# ZHSD-DDR3L.net
KiCad netlist of a schematic drawn in Altium Designer
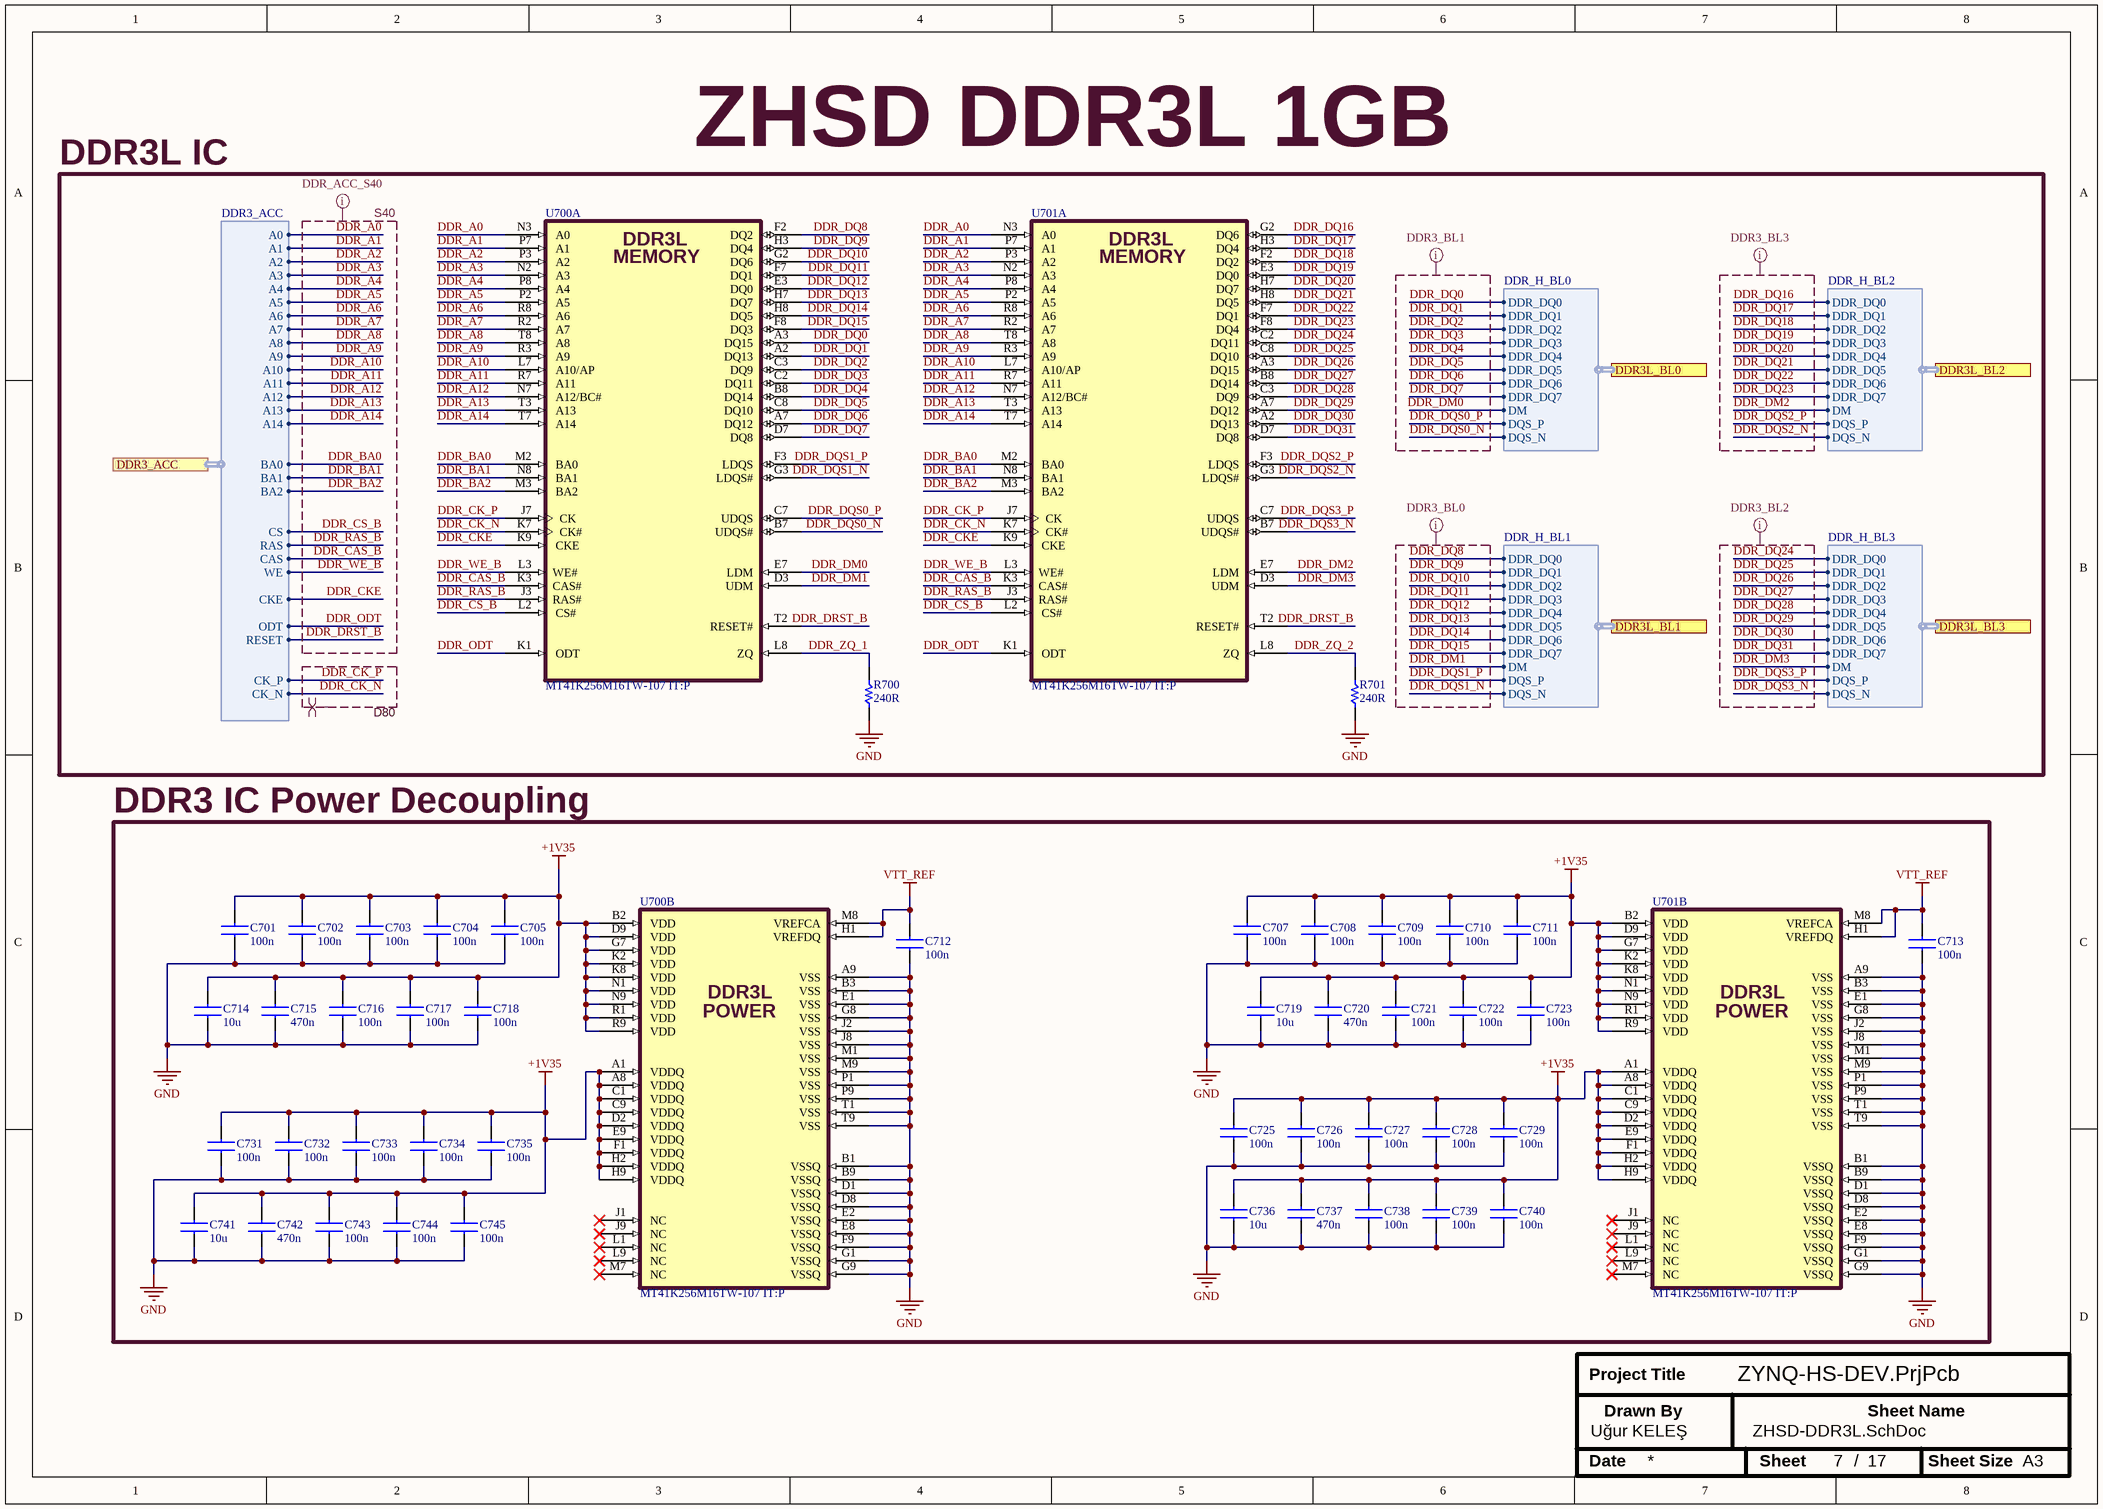
[diagram p0: ZHSD-DDR3L.SchDoc]

(export (version "E")
  (design (tool "Eeschema 10.0.6"))
  (components
    (comp (ref "C701")
      (value "100n")
      (footprint "0402CAPC1005X06N")
      (description "CAP CER 0.1UF 16V X7R 0402 (1005) ±10%")
      (fields (field (name "MANUFACTURER") "Murata Electronics") (field (name "MPN") "GRM155R71C104KA88J"))
      (libsource (lib "UK_Library_SCH") (part "GRM155R71C104KA88J"))
    )
    (comp (ref "C702")
      (value "100n")
      (footprint "0402CAPC1005X06N")
      (description "CAP CER 0.1UF 16V X7R 0402 (1005) ±10%")
      (fields (field (name "MANUFACTURER") "Murata Electronics") (field (name "MPN") "GRM155R71C104KA88J"))
      (libsource (lib "UK_Library_SCH") (part "GRM155R71C104KA88J"))
    )
    (comp (ref "C703")
      (value "100n")
      (footprint "0402CAPC1005X06N")
      (description "CAP CER 0.1UF 16V X7R 0402 (1005) ±10%")
      (fields (field (name "MANUFACTURER") "Murata Electronics") (field (name "MPN") "GRM155R71C104KA88J"))
      (libsource (lib "UK_Library_SCH") (part "GRM155R71C104KA88J"))
    )
    (comp (ref "C704")
      (value "100n")
      (footprint "0402CAPC1005X06N")
      (description "CAP CER 0.1UF 16V X7R 0402 (1005) ±10%")
      (fields (field (name "MANUFACTURER") "Murata Electronics") (field (name "MPN") "GRM155R71C104KA88J"))
      (libsource (lib "UK_Library_SCH") (part "GRM155R71C104KA88J"))
    )
    (comp (ref "C705")
      (value "100n")
      (footprint "0402CAPC1005X06N")
      (description "CAP CER 0.1UF 16V X7R 0402 (1005) ±10%")
      (fields (field (name "MANUFACTURER") "Murata Electronics") (field (name "MPN") "GRM155R71C104KA88J"))
      (libsource (lib "UK_Library_SCH") (part "GRM155R71C104KA88J"))
    )
    (comp (ref "C707")
      (value "100n")
      (footprint "0402CAPC1005X06N")
      (description "CAP CER 0.1UF 16V X7R 0402 (1005) ±10%")
      (fields (field (name "MANUFACTURER") "Murata Electronics") (field (name "MPN") "GRM155R71C104KA88J"))
      (libsource (lib "UK_Library_SCH") (part "GRM155R71C104KA88J"))
    )
    (comp (ref "C708")
      (value "100n")
      (footprint "0402CAPC1005X06N")
      (description "CAP CER 0.1UF 16V X7R 0402 (1005) ±10%")
      (fields (field (name "MANUFACTURER") "Murata Electronics") (field (name "MPN") "GRM155R71C104KA88J"))
      (libsource (lib "UK_Library_SCH") (part "GRM155R71C104KA88J"))
    )
    (comp (ref "C709")
      (value "100n")
      (footprint "0402CAPC1005X06N")
      (description "CAP CER 0.1UF 16V X7R 0402 (1005) ±10%")
      (fields (field (name "MANUFACTURER") "Murata Electronics") (field (name "MPN") "GRM155R71C104KA88J"))
      (libsource (lib "UK_Library_SCH") (part "GRM155R71C104KA88J"))
    )
    (comp (ref "C710")
      (value "100n")
      (footprint "0402CAPC1005X06N")
      (description "CAP CER 0.1UF 16V X7R 0402 (1005) ±10%")
      (fields (field (name "MANUFACTURER") "Murata Electronics") (field (name "MPN") "GRM155R71C104KA88J"))
      (libsource (lib "UK_Library_SCH") (part "GRM155R71C104KA88J"))
    )
    (comp (ref "C711")
      (value "100n")
      (footprint "0402CAPC1005X06N")
      (description "CAP CER 0.1UF 16V X7R 0402 (1005) ±10%")
      (fields (field (name "MANUFACTURER") "Murata Electronics") (field (name "MPN") "GRM155R71C104KA88J"))
      (libsource (lib "UK_Library_SCH") (part "GRM155R71C104KA88J"))
    )
    (comp (ref "C712")
      (value "100n")
      (footprint "0402CAPC1005X06N")
      (description "CAP CER 0.1UF 16V X7R 0402 (1005) ±10%")
      (fields (field (name "MANUFACTURER") "Murata Electronics") (field (name "MPN") "GRM155R71C104KA88J"))
      (libsource (lib "UK_Library_SCH") (part "GRM155R71C104KA88J"))
    )
    (comp (ref "C713")
      (value "100n")
      (footprint "0402CAPC1005X06N")
      (description "CAP CER 0.1UF 16V X7R 0402 (1005) ±10%")
      (fields (field (name "MANUFACTURER") "Murata Electronics") (field (name "MPN") "GRM155R71C104KA88J"))
      (libsource (lib "UK_Library_SCH") (part "GRM155R71C104KA88J"))
    )
    (comp (ref "C714")
      (value "10u")
      (footprint "0603CAPC1608X09N")
      (description "CAP CER 10UF 10V X7R 0603 (1608) ±20%")
      (fields (field (name "MANUFACTURER") "Murata Electronics") (field (name "MPN") "GRM188Z71A106MA73D"))
      (libsource (lib "UK_Library") (part "GRM188Z71A106MA73D"))
    )
    (comp (ref "C715")
      (value "470n")
      (footprint "0402CAPC1005X06N")
      (description "CAP CER 0.47UF 6.3V X5R 0402(1005) ±10%")
      (fields (field (name "MANUFACTURER") "Murata Electronics") (field (name "MPN") "GRM155R60J474KE19D"))
      (libsource (lib "UK_Library") (part "GRM155R60J474KE19D"))
    )
    (comp (ref "C716")
      (value "100n")
      (footprint "0402CAPC1005X06N")
      (description "CAP CER 0.1UF 16V X7R 0402 (1005) ±10%")
      (fields (field (name "MANUFACTURER") "Murata Electronics") (field (name "MPN") "GRM155R71C104KA88J"))
      (libsource (lib "UK_Library_SCH") (part "GRM155R71C104KA88J"))
    )
    (comp (ref "C717")
      (value "100n")
      (footprint "0402CAPC1005X06N")
      (description "CAP CER 0.1UF 16V X7R 0402 (1005) ±10%")
      (fields (field (name "MANUFACTURER") "Murata Electronics") (field (name "MPN") "GRM155R71C104KA88J"))
      (libsource (lib "UK_Library_SCH") (part "GRM155R71C104KA88J"))
    )
    (comp (ref "C718")
      (value "100n")
      (footprint "0402CAPC1005X06N")
      (description "CAP CER 0.1UF 16V X7R 0402 (1005) ±10%")
      (fields (field (name "MANUFACTURER") "Murata Electronics") (field (name "MPN") "GRM155R71C104KA88J"))
      (libsource (lib "UK_Library_SCH") (part "GRM155R71C104KA88J"))
    )
    (comp (ref "C719")
      (value "10u")
      (footprint "0603CAPC1608X09N")
      (description "CAP CER 10UF 10V X7R 0603 (1608) ±20%")
      (fields (field (name "MANUFACTURER") "Murata Electronics") (field (name "MPN") "GRM188Z71A106MA73D"))
      (libsource (lib "UK_Library") (part "GRM188Z71A106MA73D"))
    )
    (comp (ref "C720")
      (value "470n")
      (footprint "0402CAPC1005X06N")
      (description "CAP CER 0.47UF 6.3V X5R 0402(1005) ±10%")
      (fields (field (name "MANUFACTURER") "Murata Electronics") (field (name "MPN") "GRM155R60J474KE19D"))
      (libsource (lib "UK_Library") (part "GRM155R60J474KE19D"))
    )
    (comp (ref "C721")
      (value "100n")
      (footprint "0402CAPC1005X06N")
      (description "CAP CER 0.1UF 16V X7R 0402 (1005) ±10%")
      (fields (field (name "MANUFACTURER") "Murata Electronics") (field (name "MPN") "GRM155R71C104KA88J"))
      (libsource (lib "UK_Library_SCH") (part "GRM155R71C104KA88J"))
    )
    (comp (ref "C722")
      (value "100n")
      (footprint "0402CAPC1005X06N")
      (description "CAP CER 0.1UF 16V X7R 0402 (1005) ±10%")
      (fields (field (name "MANUFACTURER") "Murata Electronics") (field (name "MPN") "GRM155R71C104KA88J"))
      (libsource (lib "UK_Library_SCH") (part "GRM155R71C104KA88J"))
    )
    (comp (ref "C723")
      (value "100n")
      (footprint "0402CAPC1005X06N")
      (description "CAP CER 0.1UF 16V X7R 0402 (1005) ±10%")
      (fields (field (name "MANUFACTURER") "Murata Electronics") (field (name "MPN") "GRM155R71C104KA88J"))
      (libsource (lib "UK_Library_SCH") (part "GRM155R71C104KA88J"))
    )
    (comp (ref "C725")
      (value "100n")
      (footprint "0402CAPC1005X06N")
      (description "CAP CER 0.1UF 16V X7R 0402 (1005) ±10%")
      (fields (field (name "MANUFACTURER") "Murata Electronics") (field (name "MPN") "GRM155R71C104KA88J"))
      (libsource (lib "UK_Library_SCH") (part "GRM155R71C104KA88J"))
    )
    (comp (ref "C726")
      (value "100n")
      (footprint "0402CAPC1005X06N")
      (description "CAP CER 0.1UF 16V X7R 0402 (1005) ±10%")
      (fields (field (name "MANUFACTURER") "Murata Electronics") (field (name "MPN") "GRM155R71C104KA88J"))
      (libsource (lib "UK_Library_SCH") (part "GRM155R71C104KA88J"))
    )
    (comp (ref "C727")
      (value "100n")
      (footprint "0402CAPC1005X06N")
      (description "CAP CER 0.1UF 16V X7R 0402 (1005) ±10%")
      (fields (field (name "MANUFACTURER") "Murata Electronics") (field (name "MPN") "GRM155R71C104KA88J"))
      (libsource (lib "UK_Library_SCH") (part "GRM155R71C104KA88J"))
    )
    (comp (ref "C728")
      (value "100n")
      (footprint "0402CAPC1005X06N")
      (description "CAP CER 0.1UF 16V X7R 0402 (1005) ±10%")
      (fields (field (name "MANUFACTURER") "Murata Electronics") (field (name "MPN") "GRM155R71C104KA88J"))
      (libsource (lib "UK_Library_SCH") (part "GRM155R71C104KA88J"))
    )
    (comp (ref "C729")
      (value "100n")
      (footprint "0402CAPC1005X06N")
      (description "CAP CER 0.1UF 16V X7R 0402 (1005) ±10%")
      (fields (field (name "MANUFACTURER") "Murata Electronics") (field (name "MPN") "GRM155R71C104KA88J"))
      (libsource (lib "UK_Library_SCH") (part "GRM155R71C104KA88J"))
    )
    (comp (ref "C731")
      (value "100n")
      (footprint "0402CAPC1005X06N")
      (description "CAP CER 0.1UF 16V X7R 0402 (1005) ±10%")
      (fields (field (name "MANUFACTURER") "Murata Electronics") (field (name "MPN") "GRM155R71C104KA88J"))
      (libsource (lib "UK_Library_SCH") (part "GRM155R71C104KA88J"))
    )
    (comp (ref "C732")
      (value "100n")
      (footprint "0402CAPC1005X06N")
      (description "CAP CER 0.1UF 16V X7R 0402 (1005) ±10%")
      (fields (field (name "MANUFACTURER") "Murata Electronics") (field (name "MPN") "GRM155R71C104KA88J"))
      (libsource (lib "UK_Library_SCH") (part "GRM155R71C104KA88J"))
    )
    (comp (ref "C733")
      (value "100n")
      (footprint "0402CAPC1005X06N")
      (description "CAP CER 0.1UF 16V X7R 0402 (1005) ±10%")
      (fields (field (name "MANUFACTURER") "Murata Electronics") (field (name "MPN") "GRM155R71C104KA88J"))
      (libsource (lib "UK_Library_SCH") (part "GRM155R71C104KA88J"))
    )
    (comp (ref "C734")
      (value "100n")
      (footprint "0402CAPC1005X06N")
      (description "CAP CER 0.1UF 16V X7R 0402 (1005) ±10%")
      (fields (field (name "MANUFACTURER") "Murata Electronics") (field (name "MPN") "GRM155R71C104KA88J"))
      (libsource (lib "UK_Library_SCH") (part "GRM155R71C104KA88J"))
    )
    (comp (ref "C735")
      (value "100n")
      (footprint "0402CAPC1005X06N")
      (description "CAP CER 0.1UF 16V X7R 0402 (1005) ±10%")
      (fields (field (name "MANUFACTURER") "Murata Electronics") (field (name "MPN") "GRM155R71C104KA88J"))
      (libsource (lib "UK_Library_SCH") (part "GRM155R71C104KA88J"))
    )
    (comp (ref "C736")
      (value "10u")
      (footprint "0603CAPC1608X09N")
      (description "CAP CER 10UF 10V X7R 0603 (1608) ±20%")
      (fields (field (name "MANUFACTURER") "Murata Electronics") (field (name "MPN") "GRM188Z71A106MA73D"))
      (libsource (lib "UK_Library") (part "GRM188Z71A106MA73D"))
    )
    (comp (ref "C737")
      (value "470n")
      (footprint "0402CAPC1005X06N")
      (description "CAP CER 0.47UF 6.3V X5R 0402(1005) ±10%")
      (fields (field (name "MANUFACTURER") "Murata Electronics") (field (name "MPN") "GRM155R60J474KE19D"))
      (libsource (lib "UK_Library") (part "GRM155R60J474KE19D"))
    )
    (comp (ref "C738")
      (value "100n")
      (footprint "0402CAPC1005X06N")
      (description "CAP CER 0.1UF 16V X7R 0402 (1005) ±10%")
      (fields (field (name "MANUFACTURER") "Murata Electronics") (field (name "MPN") "GRM155R71C104KA88J"))
      (libsource (lib "UK_Library_SCH") (part "GRM155R71C104KA88J"))
    )
    (comp (ref "C739")
      (value "100n")
      (footprint "0402CAPC1005X06N")
      (description "CAP CER 0.1UF 16V X7R 0402 (1005) ±10%")
      (fields (field (name "MANUFACTURER") "Murata Electronics") (field (name "MPN") "GRM155R71C104KA88J"))
      (libsource (lib "UK_Library_SCH") (part "GRM155R71C104KA88J"))
    )
    (comp (ref "C740")
      (value "100n")
      (footprint "0402CAPC1005X06N")
      (description "CAP CER 0.1UF 16V X7R 0402 (1005) ±10%")
      (fields (field (name "MANUFACTURER") "Murata Electronics") (field (name "MPN") "GRM155R71C104KA88J"))
      (libsource (lib "UK_Library_SCH") (part "GRM155R71C104KA88J"))
    )
    (comp (ref "C741")
      (value "10u")
      (footprint "0603CAPC1608X09N")
      (description "CAP CER 10UF 10V X7R 0603 (1608) ±20%")
      (fields (field (name "MANUFACTURER") "Murata Electronics") (field (name "MPN") "GRM188Z71A106MA73D"))
      (libsource (lib "UK_Library") (part "GRM188Z71A106MA73D"))
    )
    (comp (ref "C742")
      (value "470n")
      (footprint "0402CAPC1005X06N")
      (description "CAP CER 0.47UF 6.3V X5R 0402(1005) ±10%")
      (fields (field (name "MANUFACTURER") "Murata Electronics") (field (name "MPN") "GRM155R60J474KE19D"))
      (libsource (lib "UK_Library") (part "GRM155R60J474KE19D"))
    )
    (comp (ref "C743")
      (value "100n")
      (footprint "0402CAPC1005X06N")
      (description "CAP CER 0.1UF 16V X7R 0402 (1005) ±10%")
      (fields (field (name "MANUFACTURER") "Murata Electronics") (field (name "MPN") "GRM155R71C104KA88J"))
      (libsource (lib "UK_Library_SCH") (part "GRM155R71C104KA88J"))
    )
    (comp (ref "C744")
      (value "100n")
      (footprint "0402CAPC1005X06N")
      (description "CAP CER 0.1UF 16V X7R 0402 (1005) ±10%")
      (fields (field (name "MANUFACTURER") "Murata Electronics") (field (name "MPN") "GRM155R71C104KA88J"))
      (libsource (lib "UK_Library_SCH") (part "GRM155R71C104KA88J"))
    )
    (comp (ref "C745")
      (value "100n")
      (footprint "0402CAPC1005X06N")
      (description "CAP CER 0.1UF 16V X7R 0402 (1005) ±10%")
      (fields (field (name "MANUFACTURER") "Murata Electronics") (field (name "MPN") "GRM155R71C104KA88J"))
      (libsource (lib "UK_Library_SCH") (part "GRM155R71C104KA88J"))
    )
    (comp (ref "R700")
      (value "240R")
      (footprint "0402RESC1005X04N")
      (description "RES 240 OHM 1% 1/16W 0402 (1005)")
      (fields (field (name "MANUFACTURER") "YAGEO") (field (name "MPN") "RC0402FR-07240RL"))
      (libsource (lib "UK_Library") (part "RC0402FR-07240RL"))
    )
    (comp (ref "R701")
      (value "240R")
      (footprint "0402RESC1005X04N")
      (description "RES 240 OHM 1% 1/16W 0402 (1005)")
      (fields (field (name "MANUFACTURER") "YAGEO") (field (name "MPN") "RC0402FR-07240RL"))
      (libsource (lib "UK_Library") (part "RC0402FR-07240RL"))
    )
    (comp (ref "U700")
      (value "MT41K256M16TW-107 IT:P")
      (footprint "BGA96C80P9X16_900X1400X110")
      (description "SDRAM - DDR3L Memory IC 4Gbit Parallel 933 MHz 20 ns 96-FBGA (8x14)")
      (fields (field (name "MANUFACTURER") "Micron Technology Inc."))
      (libsource (lib "UK_Library") (part "MT41K256M16TW-107 IT{colon}P"))
    )
    (comp (ref "U701")
      (value "MT41K256M16TW-107 IT:P")
      (footprint "BGA96C80P9X16_900X1400X110")
      (description "SDRAM - DDR3L Memory IC 4Gbit Parallel 933 MHz 20 ns 96-FBGA (8x14)")
      (fields (field (name "MANUFACTURER") "Micron Technology Inc."))
      (libsource (lib "") (part "MT41K256M16TW-107 IT{colon}P_2"))
    )
  )
  (nets
    (net (code "6") (name "+1V35") (class "Default")
      (node (ref "C701") (pin "2") (pinfunction "2_2") (pintype "passive"))
      (node (ref "C702") (pin "2") (pinfunction "2_2") (pintype "passive"))
      (node (ref "C703") (pin "2") (pinfunction "2_2") (pintype "passive"))
      (node (ref "C704") (pin "2") (pinfunction "2_2") (pintype "passive"))
      (node (ref "C705") (pin "2") (pinfunction "2_2") (pintype "passive"))
      (node (ref "C707") (pin "2") (pinfunction "2_2") (pintype "passive"))
      (node (ref "C708") (pin "2") (pinfunction "2_2") (pintype "passive"))
      (node (ref "C709") (pin "2") (pinfunction "2_2") (pintype "passive"))
      (node (ref "C710") (pin "2") (pinfunction "2_2") (pintype "passive"))
      (node (ref "C711") (pin "2") (pinfunction "2_2") (pintype "passive"))
      (node (ref "C714") (pin "2") (pinfunction "2_2") (pintype "passive"))
      (node (ref "C715") (pin "2") (pinfunction "2_2") (pintype "passive"))
      (node (ref "C716") (pin "2") (pinfunction "2_2") (pintype "passive"))
      (node (ref "C717") (pin "2") (pinfunction "2_2") (pintype "passive"))
      (node (ref "C718") (pin "2") (pinfunction "2_2") (pintype "passive"))
      (node (ref "C719") (pin "2") (pinfunction "2_2") (pintype "passive"))
      (node (ref "C720") (pin "2") (pinfunction "2_2") (pintype "passive"))
      (node (ref "C721") (pin "2") (pinfunction "2_2") (pintype "passive"))
      (node (ref "C722") (pin "2") (pinfunction "2_2") (pintype "passive"))
      (node (ref "C723") (pin "2") (pinfunction "2_2") (pintype "passive"))
      (node (ref "C725") (pin "2") (pinfunction "2_2") (pintype "passive"))
      (node (ref "C726") (pin "2") (pinfunction "2_2") (pintype "passive"))
      (node (ref "C727") (pin "2") (pinfunction "2_2") (pintype "passive"))
      (node (ref "C728") (pin "2") (pinfunction "2_2") (pintype "passive"))
      (node (ref "C729") (pin "2") (pinfunction "2_2") (pintype "passive"))
      (node (ref "C731") (pin "2") (pinfunction "2_2") (pintype "passive"))
      (node (ref "C732") (pin "2") (pinfunction "2_2") (pintype "passive"))
      (node (ref "C733") (pin "2") (pinfunction "2_2") (pintype "passive"))
      (node (ref "C734") (pin "2") (pinfunction "2_2") (pintype "passive"))
      (node (ref "C735") (pin "2") (pinfunction "2_2") (pintype "passive"))
      (node (ref "C736") (pin "2") (pinfunction "2_2") (pintype "passive"))
      (node (ref "C737") (pin "2") (pinfunction "2_2") (pintype "passive"))
      (node (ref "C738") (pin "2") (pinfunction "2_2") (pintype "passive"))
      (node (ref "C739") (pin "2") (pinfunction "2_2") (pintype "passive"))
      (node (ref "C740") (pin "2") (pinfunction "2_2") (pintype "passive"))
      (node (ref "C741") (pin "2") (pinfunction "2_2") (pintype "passive"))
      (node (ref "C742") (pin "2") (pinfunction "2_2") (pintype "passive"))
      (node (ref "C743") (pin "2") (pinfunction "2_2") (pintype "passive"))
      (node (ref "C744") (pin "2") (pinfunction "2_2") (pintype "passive"))
      (node (ref "C745") (pin "2") (pinfunction "2_2") (pintype "passive"))
      (node (ref "U700") (pin "A1") (pinfunction "_VDDQ_A1") (pintype "input"))
      (node (ref "U700") (pin "A8") (pinfunction "_VDDQ_A8") (pintype "input"))
      (node (ref "U700") (pin "B2") (pinfunction "_VDD_B2") (pintype "input"))
      (node (ref "U700") (pin "C1") (pinfunction "_VDDQ_C1") (pintype "input"))
      (node (ref "U700") (pin "C9") (pinfunction "_VDDQ_C9") (pintype "input"))
      (node (ref "U700") (pin "D2") (pinfunction "_VDDQ_D2") (pintype "input"))
      (node (ref "U700") (pin "D9") (pinfunction "_VDD_D9") (pintype "input"))
      (node (ref "U700") (pin "E9") (pinfunction "_VDDQ_E9") (pintype "input"))
      (node (ref "U700") (pin "F1") (pinfunction "_VDDQ_F1") (pintype "input"))
      (node (ref "U700") (pin "G7") (pinfunction "_VDD_G7") (pintype "input"))
      (node (ref "U700") (pin "H2") (pinfunction "_VDDQ_H2") (pintype "input"))
      (node (ref "U700") (pin "H9") (pinfunction "_VDDQ_H9") (pintype "input"))
      (node (ref "U700") (pin "K2") (pinfunction "_VDD_K2") (pintype "input"))
      (node (ref "U700") (pin "K8") (pinfunction "_VDD_K8") (pintype "input"))
      (node (ref "U700") (pin "N1") (pinfunction "_VDD_N1") (pintype "input"))
      (node (ref "U700") (pin "N9") (pinfunction "_VDD_N9") (pintype "input"))
      (node (ref "U700") (pin "R1") (pinfunction "_VDD_R1") (pintype "input"))
      (node (ref "U700") (pin "R9") (pinfunction "_VDD_R9") (pintype "input"))
      (node (ref "U701") (pin "A1") (pinfunction "_VDDQ_A1") (pintype "input"))
      (node (ref "U701") (pin "A8") (pinfunction "_VDDQ_A8") (pintype "input"))
      (node (ref "U701") (pin "B2") (pinfunction "_VDD_B2") (pintype "input"))
      (node (ref "U701") (pin "C1") (pinfunction "_VDDQ_C1") (pintype "input"))
      (node (ref "U701") (pin "C9") (pinfunction "_VDDQ_C9") (pintype "input"))
      (node (ref "U701") (pin "D2") (pinfunction "_VDDQ_D2") (pintype "input"))
      (node (ref "U701") (pin "D9") (pinfunction "_VDD_D9") (pintype "input"))
      (node (ref "U701") (pin "E9") (pinfunction "_VDDQ_E9") (pintype "input"))
      (node (ref "U701") (pin "F1") (pinfunction "_VDDQ_F1") (pintype "input"))
      (node (ref "U701") (pin "G7") (pinfunction "_VDD_G7") (pintype "input"))
      (node (ref "U701") (pin "H2") (pinfunction "_VDDQ_H2") (pintype "input"))
      (node (ref "U701") (pin "H9") (pinfunction "_VDDQ_H9") (pintype "input"))
      (node (ref "U701") (pin "K2") (pinfunction "_VDD_K2") (pintype "input"))
      (node (ref "U701") (pin "K8") (pinfunction "_VDD_K8") (pintype "input"))
      (node (ref "U701") (pin "N1") (pinfunction "_VDD_N1") (pintype "input"))
      (node (ref "U701") (pin "N9") (pinfunction "_VDD_N9") (pintype "input"))
      (node (ref "U701") (pin "R1") (pinfunction "_VDD_R1") (pintype "input"))
      (node (ref "U701") (pin "R9") (pinfunction "_VDD_R9") (pintype "input"))
    )
    (net (code "7") (name "/DDR_A0") (class "Default")
      (node (ref "U700") (pin "N3") (pinfunction "_A0_N3") (pintype "input"))
      (node (ref "U701") (pin "N3") (pinfunction "_A0_N3") (pintype "input"))
    )
    (net (code "8") (name "/DDR_A1") (class "Default")
      (node (ref "U700") (pin "P7") (pinfunction "_A1_P7") (pintype "input"))
      (node (ref "U701") (pin "P7") (pinfunction "_A1_P7") (pintype "input"))
    )
    (net (code "9") (name "/DDR_A2") (class "Default")
      (node (ref "U700") (pin "P3") (pinfunction "_A2_P3") (pintype "input"))
      (node (ref "U701") (pin "P3") (pinfunction "_A2_P3") (pintype "input"))
    )
    (net (code "10") (name "/DDR_A3") (class "Default")
      (node (ref "U700") (pin "N2") (pinfunction "_A3_N2") (pintype "input"))
      (node (ref "U701") (pin "N2") (pinfunction "_A3_N2") (pintype "input"))
    )
    (net (code "11") (name "/DDR_A4") (class "Default")
      (node (ref "U700") (pin "P8") (pinfunction "_A4_P8") (pintype "input"))
      (node (ref "U701") (pin "P8") (pinfunction "_A4_P8") (pintype "input"))
    )
    (net (code "12") (name "/DDR_A5") (class "Default")
      (node (ref "U700") (pin "P2") (pinfunction "_A5_P2") (pintype "input"))
      (node (ref "U701") (pin "P2") (pinfunction "_A5_P2") (pintype "input"))
    )
    (net (code "13") (name "/DDR_A6") (class "Default")
      (node (ref "U700") (pin "R8") (pinfunction "_A6_R8") (pintype "input"))
      (node (ref "U701") (pin "R8") (pinfunction "_A6_R8") (pintype "input"))
    )
    (net (code "14") (name "/DDR_A7") (class "Default")
      (node (ref "U700") (pin "R2") (pinfunction "_A7_R2") (pintype "input"))
      (node (ref "U701") (pin "R2") (pinfunction "_A7_R2") (pintype "input"))
    )
    (net (code "15") (name "/DDR_A8") (class "Default")
      (node (ref "U700") (pin "T8") (pinfunction "_A8_T8") (pintype "input"))
      (node (ref "U701") (pin "T8") (pinfunction "_A8_T8") (pintype "input"))
    )
    (net (code "16") (name "/DDR_A9") (class "Default")
      (node (ref "U700") (pin "R3") (pinfunction "_A9_R3") (pintype "input"))
      (node (ref "U701") (pin "R3") (pinfunction "_A9_R3") (pintype "input"))
    )
    (net (code "17") (name "/DDR_A10") (class "Default")
      (node (ref "U700") (pin "L7") (pinfunction "_A10/AP_L7") (pintype "input"))
      (node (ref "U701") (pin "L7") (pinfunction "_A10/AP_L7") (pintype "input"))
    )
    (net (code "18") (name "/DDR_A11") (class "Default")
      (node (ref "U700") (pin "R7") (pinfunction "_A11_R7") (pintype "input"))
      (node (ref "U701") (pin "R7") (pinfunction "_A11_R7") (pintype "input"))
    )
    (net (code "19") (name "/DDR_A12") (class "Default")
      (node (ref "U700") (pin "N7") (pinfunction "_A12/BC#_N7") (pintype "input"))
      (node (ref "U701") (pin "N7") (pinfunction "_A12/BC#_N7") (pintype "input"))
    )
    (net (code "20") (name "/DDR_A13") (class "Default")
      (node (ref "U700") (pin "T3") (pinfunction "_A13_T3") (pintype "input"))
      (node (ref "U701") (pin "T3") (pinfunction "_A13_T3") (pintype "input"))
    )
    (net (code "21") (name "/DDR_A14") (class "Default")
      (node (ref "U700") (pin "T7") (pinfunction "_A14_T7") (pintype "input"))
      (node (ref "U701") (pin "T7") (pinfunction "_A14_T7") (pintype "input"))
    )
    (net (code "22") (name "/DDR_BA0") (class "Default")
      (node (ref "U700") (pin "M2") (pinfunction "_BA0_M2") (pintype "input"))
      (node (ref "U701") (pin "M2") (pinfunction "_BA0_M2") (pintype "input"))
    )
    (net (code "23") (name "/DDR_BA1") (class "Default")
      (node (ref "U700") (pin "N8") (pinfunction "_BA1_N8") (pintype "input"))
      (node (ref "U701") (pin "N8") (pinfunction "_BA1_N8") (pintype "input"))
    )
    (net (code "24") (name "/DDR_BA2") (class "Default")
      (node (ref "U700") (pin "M3") (pinfunction "_BA2_M3") (pintype "input"))
      (node (ref "U701") (pin "M3") (pinfunction "_BA2_M3") (pintype "input"))
    )
    (net (code "25") (name "/DDR_CAS_B") (class "Default")
      (node (ref "U700") (pin "K3") (pinfunction "CAS#_K3") (pintype "input"))
      (node (ref "U701") (pin "K3") (pinfunction "CAS#_K3") (pintype "input"))
    )
    (net (code "26") (name "/DDR_CKE") (class "Default")
      (node (ref "U700") (pin "K9") (pinfunction "_CKE_K9") (pintype "input"))
      (node (ref "U701") (pin "K9") (pinfunction "_CKE_K9") (pintype "input"))
    )
    (net (code "27") (name "/DDR_CK_N") (class "Default")
      (node (ref "U700") (pin "K7") (pinfunction "_CK#_K7") (pintype "input"))
      (node (ref "U701") (pin "K7") (pinfunction "_CK#_K7") (pintype "input"))
    )
    (net (code "28") (name "/DDR_CK_P") (class "Default")
      (node (ref "U700") (pin "J7") (pinfunction "_CK_J7") (pintype "input"))
      (node (ref "U701") (pin "J7") (pinfunction "_CK_J7") (pintype "input"))
    )
    (net (code "29") (name "/DDR_CS_B") (class "Default")
      (node (ref "U700") (pin "L2") (pinfunction "_CS#_L2") (pintype "input"))
      (node (ref "U701") (pin "L2") (pinfunction "_CS#_L2") (pintype "input"))
    )
    (net (code "30") (name "/DDR_DM0") (class "Default")
      (node (ref "U700") (pin "E7") (pinfunction "_LDM_E7") (pintype "input"))
    )
    (net (code "31") (name "/DDR_DM1") (class "Default")
      (node (ref "U700") (pin "D3") (pinfunction "_UDM_D3") (pintype "input"))
    )
    (net (code "32") (name "/DDR_DM2") (class "Default")
      (node (ref "U701") (pin "E7") (pinfunction "_LDM_E7") (pintype "input"))
    )
    (net (code "33") (name "/DDR_DM3") (class "Default")
      (node (ref "U701") (pin "D3") (pinfunction "_UDM_D3") (pintype "input"))
    )
    (net (code "34") (name "/DDR_DQ0") (class "Default")
      (node (ref "U700") (pin "A3") (pinfunction "_DQ15_A3") (pintype "bidirectional"))
    )
    (net (code "35") (name "/DDR_DQ1") (class "Default")
      (node (ref "U700") (pin "A2") (pinfunction "_DQ13_A2") (pintype "bidirectional"))
    )
    (net (code "36") (name "/DDR_DQ2") (class "Default")
      (node (ref "U700") (pin "C3") (pinfunction "_DQ9_C3") (pintype "bidirectional"))
    )
    (net (code "37") (name "/DDR_DQ3") (class "Default")
      (node (ref "U700") (pin "C2") (pinfunction "_DQ11_C2") (pintype "bidirectional"))
    )
    (net (code "38") (name "/DDR_DQ4") (class "Default")
      (node (ref "U700") (pin "B8") (pinfunction "_DQ14_B8") (pintype "bidirectional"))
    )
    (net (code "39") (name "/DDR_DQ5") (class "Default")
      (node (ref "U700") (pin "C8") (pinfunction "_DQ10_C8") (pintype "bidirectional"))
    )
    (net (code "40") (name "/DDR_DQ6") (class "Default")
      (node (ref "U700") (pin "A7") (pinfunction "_DQ12_A7") (pintype "bidirectional"))
    )
    (net (code "41") (name "/DDR_DQ7") (class "Default")
      (node (ref "U700") (pin "D7") (pinfunction "_DQ8_D7") (pintype "bidirectional"))
    )
    (net (code "42") (name "/DDR_DQ8") (class "Default")
      (node (ref "U700") (pin "F2") (pinfunction "_DQ2_F2") (pintype "bidirectional"))
    )
    (net (code "43") (name "/DDR_DQ9") (class "Default")
      (node (ref "U700") (pin "H3") (pinfunction "_DQ4_H3") (pintype "bidirectional"))
    )
    (net (code "44") (name "/DDR_DQ10") (class "Default")
      (node (ref "U700") (pin "G2") (pinfunction "_DQ6_G2") (pintype "bidirectional"))
    )
    (net (code "45") (name "/DDR_DQ11") (class "Default")
      (node (ref "U700") (pin "F7") (pinfunction "_DQ1_F7") (pintype "bidirectional"))
    )
    (net (code "46") (name "/DDR_DQ12") (class "Default")
      (node (ref "U700") (pin "E3") (pinfunction "_DQ0_E3") (pintype "bidirectional"))
    )
    (net (code "47") (name "/DDR_DQ13") (class "Default")
      (node (ref "U700") (pin "H7") (pinfunction "_DQ7_H7") (pintype "bidirectional"))
    )
    (net (code "48") (name "/DDR_DQ14") (class "Default")
      (node (ref "U700") (pin "H8") (pinfunction "_DQ5_H8") (pintype "bidirectional"))
    )
    (net (code "49") (name "/DDR_DQ15") (class "Default")
      (node (ref "U700") (pin "F8") (pinfunction "_DQ3_F8") (pintype "bidirectional"))
    )
    (net (code "50") (name "/DDR_DQ16") (class "Default")
      (node (ref "U701") (pin "G2") (pinfunction "_DQ6_G2") (pintype "bidirectional"))
    )
    (net (code "51") (name "/DDR_DQ17") (class "Default")
      (node (ref "U701") (pin "H3") (pinfunction "_DQ4_H3") (pintype "bidirectional"))
    )
    (net (code "52") (name "/DDR_DQ18") (class "Default")
      (node (ref "U701") (pin "F2") (pinfunction "_DQ2_F2") (pintype "bidirectional"))
    )
    (net (code "53") (name "/DDR_DQ19") (class "Default")
      (node (ref "U701") (pin "E3") (pinfunction "_DQ0_E3") (pintype "bidirectional"))
    )
    (net (code "54") (name "/DDR_DQ20") (class "Default")
      (node (ref "U701") (pin "H7") (pinfunction "_DQ7_H7") (pintype "bidirectional"))
    )
    (net (code "55") (name "/DDR_DQ21") (class "Default")
      (node (ref "U701") (pin "H8") (pinfunction "_DQ5_H8") (pintype "bidirectional"))
    )
    (net (code "56") (name "/DDR_DQ22") (class "Default")
      (node (ref "U701") (pin "F7") (pinfunction "_DQ1_F7") (pintype "bidirectional"))
    )
    (net (code "57") (name "/DDR_DQ23") (class "Default")
      (node (ref "U701") (pin "F8") (pinfunction "_DQ4_F8") (pintype "bidirectional"))
    )
    (net (code "58") (name "/DDR_DQ24") (class "Default")
      (node (ref "U701") (pin "C2") (pinfunction "_DQ11_C2") (pintype "bidirectional"))
    )
    (net (code "59") (name "/DDR_DQ25") (class "Default")
      (node (ref "U701") (pin "C8") (pinfunction "_DQ10_C8") (pintype "bidirectional"))
    )
    (net (code "60") (name "/DDR_DQ26") (class "Default")
      (node (ref "U701") (pin "A3") (pinfunction "_DQ15_A3") (pintype "bidirectional"))
    )
    (net (code "61") (name "/DDR_DQ27") (class "Default")
      (node (ref "U701") (pin "B8") (pinfunction "_DQ14_B8") (pintype "bidirectional"))
    )
    (net (code "62") (name "/DDR_DQ28") (class "Default")
      (node (ref "U701") (pin "C3") (pinfunction "_DQ9_C3") (pintype "bidirectional"))
    )
    (net (code "63") (name "/DDR_DQ29") (class "Default")
      (node (ref "U701") (pin "A7") (pinfunction "_DQ12_A7") (pintype "bidirectional"))
    )
    (net (code "64") (name "/DDR_DQ30") (class "Default")
      (node (ref "U701") (pin "A2") (pinfunction "_DQ13_A2") (pintype "bidirectional"))
    )
    (net (code "65") (name "/DDR_DQ31") (class "Default")
      (node (ref "U701") (pin "D7") (pinfunction "_DQ8_D7") (pintype "bidirectional"))
    )
    (net (code "66") (name "/DDR_DQS0_N") (class "Default")
      (node (ref "U700") (pin "B7") (pinfunction "_UDQS#_B7") (pintype "bidirectional"))
    )
    (net (code "67") (name "/DDR_DQS0_P") (class "Default")
      (node (ref "U700") (pin "C7") (pinfunction "_UDQS_C7") (pintype "bidirectional"))
    )
    (net (code "68") (name "/DDR_DQS1_N") (class "Default")
      (node (ref "U700") (pin "G3") (pinfunction "_LDQS#_G3") (pintype "bidirectional"))
    )
    (net (code "69") (name "/DDR_DQS1_P") (class "Default")
      (node (ref "U700") (pin "F3") (pinfunction "_LDQS_F3") (pintype "bidirectional"))
    )
    (net (code "70") (name "/DDR_DQS2_N") (class "Default")
      (node (ref "U701") (pin "G3") (pinfunction "_LDQS#_G3") (pintype "bidirectional"))
    )
    (net (code "71") (name "/DDR_DQS2_P") (class "Default")
      (node (ref "U701") (pin "F3") (pinfunction "_LDQS_F3") (pintype "bidirectional"))
    )
    (net (code "72") (name "/DDR_DQS3_N") (class "Default")
      (node (ref "U701") (pin "B7") (pinfunction "_UDQS#_B7") (pintype "bidirectional"))
    )
    (net (code "73") (name "/DDR_DQS3_P") (class "Default")
      (node (ref "U701") (pin "C7") (pinfunction "_UDQS_C7") (pintype "bidirectional"))
    )
    (net (code "74") (name "/DDR_DRST_B") (class "Default")
      (node (ref "U700") (pin "T2") (pinfunction "_RESET#_T2") (pintype "input"))
      (node (ref "U701") (pin "T2") (pinfunction "_RESET#_T2") (pintype "input"))
    )
    (net (code "75") (name "/DDR_ODT") (class "Default")
      (node (ref "U700") (pin "K1") (pinfunction "_ODT_K1") (pintype "input"))
      (node (ref "U701") (pin "K1") (pinfunction "_ODT_K1") (pintype "input"))
    )
    (net (code "76") (name "/DDR_RAS_B") (class "Default")
      (node (ref "U700") (pin "J3") (pinfunction "RAS#_J3") (pintype "input"))
      (node (ref "U701") (pin "J3") (pinfunction "RAS#_J3") (pintype "input"))
    )
    (net (code "77") (name "/DDR_WE_B") (class "Default")
      (node (ref "U700") (pin "L3") (pinfunction "WE#_L3") (pintype "input"))
      (node (ref "U701") (pin "L3") (pinfunction "WE#_L3") (pintype "input"))
    )
    (net (code "78") (name "/DDR_ZQ_1") (class "Default")
      (node (ref "R700") (pin "2") (pinfunction "2_2") (pintype "passive"))
      (node (ref "U700") (pin "L8") (pinfunction "ZQ_L8") (pintype "input"))
    )
    (net (code "79") (name "/DDR_ZQ_2") (class "Default")
      (node (ref "R701") (pin "2") (pinfunction "2_2") (pintype "passive"))
      (node (ref "U701") (pin "L8") (pinfunction "ZQ_L8") (pintype "input"))
    )
    (net (code "85") (name "GND") (class "Default")
      (node (ref "C701") (pin "1") (pinfunction "1_1") (pintype "passive"))
      (node (ref "C702") (pin "1") (pinfunction "1_1") (pintype "passive"))
      (node (ref "C703") (pin "1") (pinfunction "1_1") (pintype "passive"))
      (node (ref "C704") (pin "1") (pinfunction "1_1") (pintype "passive"))
      (node (ref "C705") (pin "1") (pinfunction "1_1") (pintype "passive"))
      (node (ref "C707") (pin "1") (pinfunction "1_1") (pintype "passive"))
      (node (ref "C708") (pin "1") (pinfunction "1_1") (pintype "passive"))
      (node (ref "C709") (pin "1") (pinfunction "1_1") (pintype "passive"))
      (node (ref "C710") (pin "1") (pinfunction "1_1") (pintype "passive"))
      (node (ref "C711") (pin "1") (pinfunction "1_1") (pintype "passive"))
      (node (ref "C712") (pin "1") (pinfunction "1_1") (pintype "passive"))
      (node (ref "C713") (pin "1") (pinfunction "1_1") (pintype "passive"))
      (node (ref "C714") (pin "1") (pinfunction "1_1") (pintype "passive"))
      (node (ref "C715") (pin "1") (pinfunction "1_1") (pintype "passive"))
      (node (ref "C716") (pin "1") (pinfunction "1_1") (pintype "passive"))
      (node (ref "C717") (pin "1") (pinfunction "1_1") (pintype "passive"))
      (node (ref "C718") (pin "1") (pinfunction "1_1") (pintype "passive"))
      (node (ref "C719") (pin "1") (pinfunction "1_1") (pintype "passive"))
      (node (ref "C720") (pin "1") (pinfunction "1_1") (pintype "passive"))
      (node (ref "C721") (pin "1") (pinfunction "1_1") (pintype "passive"))
      (node (ref "C722") (pin "1") (pinfunction "1_1") (pintype "passive"))
      (node (ref "C723") (pin "1") (pinfunction "1_1") (pintype "passive"))
      (node (ref "C725") (pin "1") (pinfunction "1_1") (pintype "passive"))
      (node (ref "C726") (pin "1") (pinfunction "1_1") (pintype "passive"))
      (node (ref "C727") (pin "1") (pinfunction "1_1") (pintype "passive"))
      (node (ref "C728") (pin "1") (pinfunction "1_1") (pintype "passive"))
      (node (ref "C729") (pin "1") (pinfunction "1_1") (pintype "passive"))
      (node (ref "C731") (pin "1") (pinfunction "1_1") (pintype "passive"))
      (node (ref "C732") (pin "1") (pinfunction "1_1") (pintype "passive"))
      (node (ref "C733") (pin "1") (pinfunction "1_1") (pintype "passive"))
      (node (ref "C734") (pin "1") (pinfunction "1_1") (pintype "passive"))
      (node (ref "C735") (pin "1") (pinfunction "1_1") (pintype "passive"))
      (node (ref "C736") (pin "1") (pinfunction "1_1") (pintype "passive"))
      (node (ref "C737") (pin "1") (pinfunction "1_1") (pintype "passive"))
      (node (ref "C738") (pin "1") (pinfunction "1_1") (pintype "passive"))
      (node (ref "C739") (pin "1") (pinfunction "1_1") (pintype "passive"))
      (node (ref "C740") (pin "1") (pinfunction "1_1") (pintype "passive"))
      (node (ref "C741") (pin "1") (pinfunction "1_1") (pintype "passive"))
      (node (ref "C742") (pin "1") (pinfunction "1_1") (pintype "passive"))
      (node (ref "C743") (pin "1") (pinfunction "1_1") (pintype "passive"))
      (node (ref "C744") (pin "1") (pinfunction "1_1") (pintype "passive"))
      (node (ref "C745") (pin "1") (pinfunction "1_1") (pintype "passive"))
      (node (ref "R700") (pin "1") (pinfunction "1_1") (pintype "passive"))
      (node (ref "R701") (pin "1") (pinfunction "1_1") (pintype "passive"))
      (node (ref "U700") (pin "A9") (pinfunction "_VSS_A9") (pintype "input"))
      (node (ref "U700") (pin "B1") (pinfunction "_VSSQ_B1") (pintype "input"))
      (node (ref "U700") (pin "B3") (pinfunction "_VSS_B3") (pintype "input"))
      (node (ref "U700") (pin "B9") (pinfunction "_VSSQ_B9") (pintype "input"))
      (node (ref "U700") (pin "D1") (pinfunction "_VSSQ_D1") (pintype "input"))
      (node (ref "U700") (pin "D8") (pinfunction "_VSSQ_D8") (pintype "input"))
      (node (ref "U700") (pin "E1") (pinfunction "_VSS_E1") (pintype "input"))
      (node (ref "U700") (pin "E2") (pinfunction "_VSSQ_E2") (pintype "input"))
      (node (ref "U700") (pin "E8") (pinfunction "_VSSQ_E8") (pintype "input"))
      (node (ref "U700") (pin "F9") (pinfunction "_VSSQ_F9") (pintype "input"))
      (node (ref "U700") (pin "G1") (pinfunction "_VSSQ_G1") (pintype "input"))
      (node (ref "U700") (pin "G8") (pinfunction "_VSS_G8") (pintype "input"))
      (node (ref "U700") (pin "G9") (pinfunction "_VSSQ_G9") (pintype "input"))
      (node (ref "U700") (pin "J2") (pinfunction "_VSS_J2") (pintype "input"))
      (node (ref "U700") (pin "J8") (pinfunction "_VSS_J8") (pintype "input"))
      (node (ref "U700") (pin "M1") (pinfunction "_VSS_M1") (pintype "input"))
      (node (ref "U700") (pin "M9") (pinfunction "_VSS_M9") (pintype "input"))
      (node (ref "U700") (pin "P1") (pinfunction "_VSS_P1") (pintype "input"))
      (node (ref "U700") (pin "P9") (pinfunction "_VSS_P9") (pintype "input"))
      (node (ref "U700") (pin "T1") (pinfunction "_VSS_T1") (pintype "input"))
      (node (ref "U700") (pin "T9") (pinfunction "_VSS_T9") (pintype "input"))
      (node (ref "U701") (pin "A9") (pinfunction "_VSS_A9") (pintype "input"))
      (node (ref "U701") (pin "B1") (pinfunction "_VSSQ_B1") (pintype "input"))
      (node (ref "U701") (pin "B3") (pinfunction "_VSS_B3") (pintype "input"))
      (node (ref "U701") (pin "B9") (pinfunction "_VSSQ_B9") (pintype "input"))
      (node (ref "U701") (pin "D1") (pinfunction "_VSSQ_D1") (pintype "input"))
      (node (ref "U701") (pin "D8") (pinfunction "_VSSQ_D8") (pintype "input"))
      (node (ref "U701") (pin "E1") (pinfunction "_VSS_E1") (pintype "input"))
      (node (ref "U701") (pin "E2") (pinfunction "_VSSQ_E2") (pintype "input"))
      (node (ref "U701") (pin "E8") (pinfunction "_VSSQ_E8") (pintype "input"))
      (node (ref "U701") (pin "F9") (pinfunction "_VSSQ_F9") (pintype "input"))
      (node (ref "U701") (pin "G1") (pinfunction "_VSSQ_G1") (pintype "input"))
      (node (ref "U701") (pin "G8") (pinfunction "_VSS_G8") (pintype "input"))
      (node (ref "U701") (pin "G9") (pinfunction "_VSSQ_G9") (pintype "input"))
      (node (ref "U701") (pin "J2") (pinfunction "_VSS_J2") (pintype "input"))
      (node (ref "U701") (pin "J8") (pinfunction "_VSS_J8") (pintype "input"))
      (node (ref "U701") (pin "M1") (pinfunction "_VSS_M1") (pintype "input"))
      (node (ref "U701") (pin "M9") (pinfunction "_VSS_M9") (pintype "input"))
      (node (ref "U701") (pin "P1") (pinfunction "_VSS_P1") (pintype "input"))
      (node (ref "U701") (pin "P9") (pinfunction "_VSS_P9") (pintype "input"))
      (node (ref "U701") (pin "T1") (pinfunction "_VSS_T1") (pintype "input"))
      (node (ref "U701") (pin "T9") (pinfunction "_VSS_T9") (pintype "input"))
    )
    (net (code "86") (name "VTT_REF") (class "Default")
      (node (ref "C712") (pin "2") (pinfunction "2_2") (pintype "passive"))
      (node (ref "C713") (pin "2") (pinfunction "2_2") (pintype "passive"))
      (node (ref "U700") (pin "H1") (pinfunction "_VREFDQ_H1") (pintype "input"))
      (node (ref "U700") (pin "M8") (pinfunction "_VREFCA_M8") (pintype "input"))
      (node (ref "U701") (pin "H1") (pinfunction "_VREFDQ_H1") (pintype "input"))
      (node (ref "U701") (pin "M8") (pinfunction "_VREFCA_M8") (pintype "input"))
    )
    (net (code "87") (name "unconnected-(U700B-_NC-PadJ1)") (class "Default")
      (node (ref "U700") (pin "J1") (pinfunction "_NC_J1") (pintype "input+no_connect"))
    )
    (net (code "88") (name "unconnected-(U700B-_NC-PadJ9)") (class "Default")
      (node (ref "U700") (pin "J9") (pinfunction "_NC_J9") (pintype "input+no_connect"))
    )
    (net (code "89") (name "unconnected-(U700B-_NC-PadL1)") (class "Default")
      (node (ref "U700") (pin "L1") (pinfunction "_NC_L1") (pintype "input+no_connect"))
    )
    (net (code "90") (name "unconnected-(U700B-_NC-PadL9)") (class "Default")
      (node (ref "U700") (pin "L9") (pinfunction "_NC_L9") (pintype "input+no_connect"))
    )
    (net (code "91") (name "unconnected-(U700B-_NC-PadM7)") (class "Default")
      (node (ref "U700") (pin "M7") (pinfunction "_NC_M7") (pintype "input+no_connect"))
    )
    (net (code "92") (name "unconnected-(U701B-_NC-PadJ1)") (class "Default")
      (node (ref "U701") (pin "J1") (pinfunction "_NC_J1") (pintype "input+no_connect"))
    )
    (net (code "93") (name "unconnected-(U701B-_NC-PadJ9)") (class "Default")
      (node (ref "U701") (pin "J9") (pinfunction "_NC_J9") (pintype "input+no_connect"))
    )
    (net (code "94") (name "unconnected-(U701B-_NC-PadL1)") (class "Default")
      (node (ref "U701") (pin "L1") (pinfunction "_NC_L1") (pintype "input+no_connect"))
    )
    (net (code "95") (name "unconnected-(U701B-_NC-PadL9)") (class "Default")
      (node (ref "U701") (pin "L9") (pinfunction "_NC_L9") (pintype "input+no_connect"))
    )
    (net (code "96") (name "unconnected-(U701B-_NC-PadM7)") (class "Default")
      (node (ref "U701") (pin "M7") (pinfunction "_NC_M7") (pintype "input+no_connect"))
    )
  )
)
